# 15V_PS.net
KiCad netlist of a schematic drawn in EAGLE
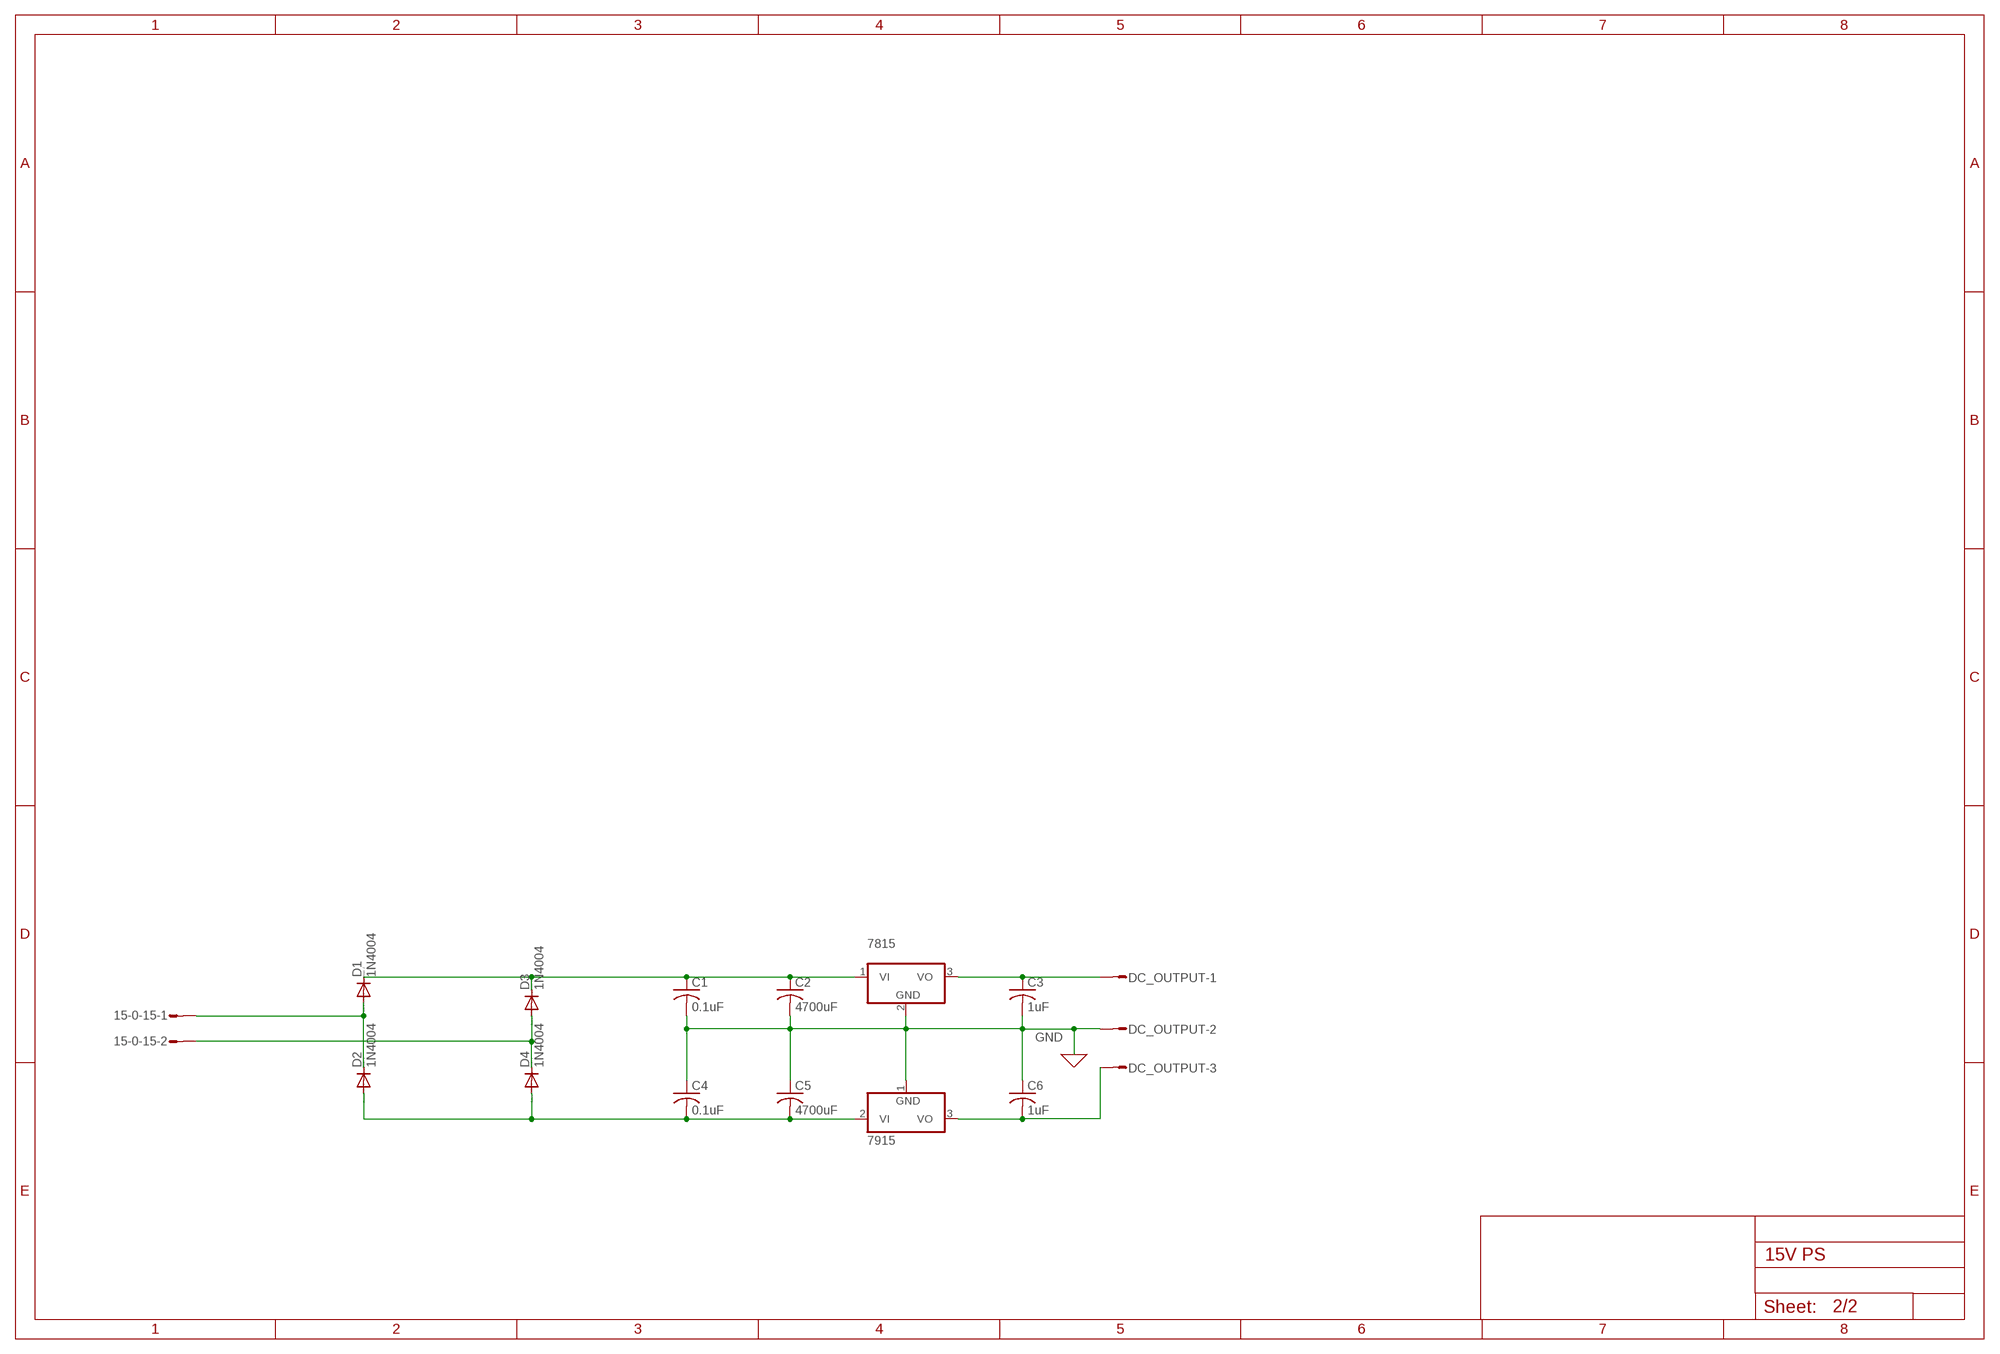
[diagram p0: schematic, sheet 2]

(export (version "E")
  (design (tool "Eeschema 10.0.6"))
  (components
    (comp (ref "15-0-15")
      (value "L02P")
      (footprint "eagle-import:L02P")
      (libsource (lib "eagle-import") (part "L02P"))
    )
    (comp (ref "7815")
      (value "7815T")
      (footprint "eagle-import:TO220H")
      (libsource (lib "eagle-import") (part "78T15"))
    )
    (comp (ref "7915")
      (value "7915T")
      (footprint "eagle-import:TO220H")
      (libsource (lib "eagle-import") (part "79T15"))
    )
    (comp (ref "C1")
      (value "0.1uF")
      (footprint "eagle-import:C025-024X044")
      (libsource (lib "eagle-import") (part "C-US025-024X044"))
    )
    (comp (ref "C2")
      (value "4700uF")
      (footprint "eagle-import:C025-024X044")
      (libsource (lib "eagle-import") (part "C-US025-024X044"))
    )
    (comp (ref "C3")
      (value "1uF")
      (footprint "eagle-import:C025-024X044")
      (libsource (lib "eagle-import") (part "C-US025-024X044"))
    )
    (comp (ref "C4")
      (value "0.1uF")
      (footprint "eagle-import:C025-024X044")
      (libsource (lib "eagle-import") (part "C-US025-024X044"))
    )
    (comp (ref "C5")
      (value "4700uF")
      (footprint "eagle-import:C025-024X044")
      (libsource (lib "eagle-import") (part "C-US025-024X044"))
    )
    (comp (ref "C6")
      (value "1uF")
      (footprint "eagle-import:C025-024X044")
      (libsource (lib "eagle-import") (part "C-US025-024X044"))
    )
    (comp (ref "D1")
      (value "1N4004")
      (footprint "eagle-import:DO41-10")
      (libsource (lib "eagle-import") (part "1N4004"))
    )
    (comp (ref "D2")
      (value "1N4004")
      (footprint "eagle-import:DO41-10")
      (libsource (lib "eagle-import") (part "1N4004"))
    )
    (comp (ref "D3")
      (value "1N4004")
      (footprint "eagle-import:DO41-10")
      (libsource (lib "eagle-import") (part "1N4004"))
    )
    (comp (ref "D4")
      (value "1N4004")
      (footprint "eagle-import:DO41-10")
      (libsource (lib "eagle-import") (part "1N4004"))
    )
    (comp (ref "DC_OUTPUT")
      (value "L03P")
      (footprint "eagle-import:L03P")
      (fields (field (name "SPICEPREFIX") "X"))
      (libsource (lib "eagle-import") (part "L03P"))
    )
  )
  (nets
    (net (code "1") (name "GND") (class "Default")
      (node (ref "7815") (pin "2") (pinfunction "GND_2") (pintype "passive"))
      (node (ref "7915") (pin "1") (pinfunction "GND_1") (pintype "passive"))
      (node (ref "C1") (pin "2") (pinfunction "2_2") (pintype "passive"))
      (node (ref "C2") (pin "2") (pinfunction "2_2") (pintype "passive"))
      (node (ref "C3") (pin "2") (pinfunction "2_2") (pintype "passive"))
      (node (ref "C4") (pin "1") (pinfunction "1_1") (pintype "passive"))
      (node (ref "C5") (pin "1") (pinfunction "1_1") (pintype "passive"))
      (node (ref "C6") (pin "1") (pinfunction "1_1") (pintype "passive"))
      (node (ref "DC_OUTPUT") (pin "2") (pinfunction "S_2") (pintype "passive"))
    )
    (net (code "2") (name "Net-(15-0-15A-S)") (class "Default")
      (node (ref "15-0-15") (pin "1") (pinfunction "S_1") (pintype "passive"))
      (node (ref "D1") (pin "A") (pinfunction "A_A") (pintype "passive"))
      (node (ref "D2") (pin "C") (pinfunction "C_C") (pintype "passive"))
    )
    (net (code "3") (name "Net-(15-0-15B-S)") (class "Default")
      (node (ref "15-0-15") (pin "2") (pinfunction "S_2") (pintype "passive"))
      (node (ref "D3") (pin "A") (pinfunction "A_A") (pintype "passive"))
      (node (ref "D4") (pin "C") (pinfunction "C_C") (pintype "passive"))
    )
    (net (code "4") (name "Net-(7815-VI)") (class "Default")
      (node (ref "7815") (pin "1") (pinfunction "VI_1") (pintype "input"))
      (node (ref "C1") (pin "1") (pinfunction "1_1") (pintype "passive"))
      (node (ref "C2") (pin "1") (pinfunction "1_1") (pintype "passive"))
      (node (ref "D1") (pin "C") (pinfunction "C_C") (pintype "passive"))
      (node (ref "D3") (pin "C") (pinfunction "C_C") (pintype "passive"))
    )
    (net (code "5") (name "Net-(7815-VO)") (class "Default")
      (node (ref "7815") (pin "3") (pinfunction "VO_3") (pintype "passive"))
      (node (ref "C3") (pin "1") (pinfunction "1_1") (pintype "passive"))
      (node (ref "DC_OUTPUT") (pin "1") (pinfunction "S_1") (pintype "passive"))
    )
    (net (code "6") (name "Net-(7915-VI)") (class "Default")
      (node (ref "7915") (pin "2") (pinfunction "VI_2") (pintype "input"))
      (node (ref "C4") (pin "2") (pinfunction "2_2") (pintype "passive"))
      (node (ref "C5") (pin "2") (pinfunction "2_2") (pintype "passive"))
      (node (ref "D2") (pin "A") (pinfunction "A_A") (pintype "passive"))
      (node (ref "D4") (pin "A") (pinfunction "A_A") (pintype "passive"))
    )
    (net (code "7") (name "Net-(7915-VO)") (class "Default")
      (node (ref "7915") (pin "3") (pinfunction "VO_3") (pintype "passive"))
      (node (ref "C6") (pin "2") (pinfunction "2_2") (pintype "passive"))
      (node (ref "DC_OUTPUT") (pin "3") (pinfunction "S_3") (pintype "passive"))
    )
  )
)
